# CAN.net
KiCad netlist of a schematic drawn in Altium Designer
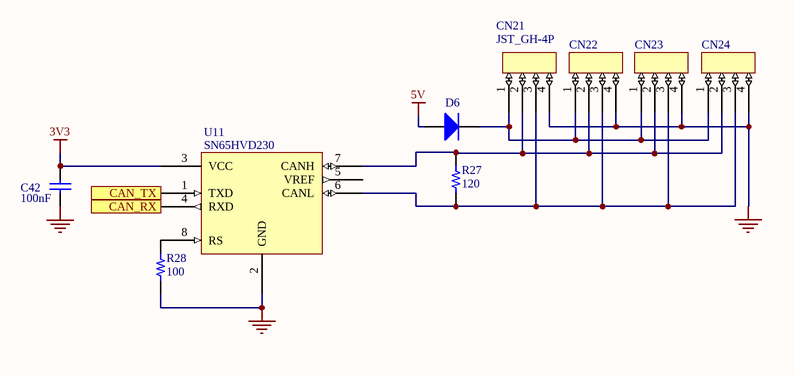
[diagram p0: CAN.SchDoc]

(export (version "E")
  (design (tool "Eeschema 10.0.6"))
  (components
    (comp (ref "C42")
      (value "100nF")
      (footprint "0402")
      (fields (field (name "Comment") "Cap") (field (name "PUBLISHER") "Altium Limited"))
      (libsource (lib "Parts") (part "Cap"))
    )
    (comp (ref "CN21")
      (value "JST_GH-4P")
      (footprint "JST_GH-4P")
      (libsource (lib "Parts") (part "JST_GH-4P"))
    )
    (comp (ref "CN22")
      (value "JST_GH-4P")
      (footprint "JST_GH-4P")
      (libsource (lib "Parts") (part "JST_GH-4P"))
    )
    (comp (ref "CN23")
      (value "JST_GH-4P")
      (footprint "JST_GH-4P")
      (libsource (lib "Parts") (part "JST_GH-4P"))
    )
    (comp (ref "CN24")
      (value "JST_GH-4P")
      (footprint "JST_GH-4P")
      (libsource (lib "Parts") (part "JST_GH-4P"))
    )
    (comp (ref "D6") (value "SS12F") (footprint "SMAF_DIODE") (libsource (lib "Parts") (part "SS12F")))
    (comp (ref "R27")
      (value "120")
      (footprint "2010_SMD_Resistor")
      (libsource (lib "Parts") (part "Resistor"))
    )
    (comp (ref "R28")
      (value "100")
      (footprint "0805 - duplicate")
      (libsource (lib "Parts") (part "Resistor"))
    )
    (comp (ref "U11")
      (value "SN65HVD230")
      (footprint "SOIC8-TI_CAN")
      (description "CAN Transceiver")
      (libsource (lib "Parts") (part "SN65HVD230"))
    )
  )
  (nets
    (net (code "1") (name "/CAN_RX") (class "Default")
      (node (ref "U11") (pin "4") (pinfunction "RXD_4") (pintype "output"))
    )
    (net (code "2") (name "/CAN_TX") (class "Default")
      (node (ref "U11") (pin "1") (pinfunction "TXD_1") (pintype "input"))
    )
    (net (code "3") (name "3V3") (class "Default")
      (node (ref "C42") (pin "2") (pinfunction "2_2") (pintype "passive"))
      (node (ref "U11") (pin "3") (pinfunction "VCC_3") (pintype "power_in"))
    )
    (net (code "4") (name "5V") (class "Default")
      (node (ref "D6") (pin "1") (pinfunction "A_1") (pintype "passive"))
    )
    (net (code "5") (name "GND") (class "Default")
      (node (ref "C42") (pin "1") (pinfunction "1_1") (pintype "passive"))
      (node (ref "CN21") (pin "4") (pintype "bidirectional"))
      (node (ref "CN22") (pin "4") (pintype "bidirectional"))
      (node (ref "CN23") (pin "4") (pintype "bidirectional"))
      (node (ref "CN24") (pin "4") (pintype "bidirectional"))
      (node (ref "R28") (pin "1") (pinfunction "1_1") (pintype "passive"))
      (node (ref "U11") (pin "2") (pinfunction "GND_2") (pintype "power_in"))
    )
    (net (code "6") (name "Net-(D6-K)") (class "Default")
      (node (ref "CN21") (pin "1") (pintype "bidirectional"))
      (node (ref "CN22") (pin "1") (pintype "bidirectional"))
      (node (ref "CN23") (pin "1") (pintype "bidirectional"))
      (node (ref "CN24") (pin "1") (pintype "bidirectional"))
      (node (ref "D6") (pin "2") (pinfunction "K_2") (pintype "passive"))
    )
    (net (code "7") (name "Net-(U11-CANH)") (class "Default")
      (node (ref "CN21") (pin "2") (pintype "bidirectional"))
      (node (ref "CN22") (pin "2") (pintype "bidirectional"))
      (node (ref "CN23") (pin "2") (pintype "bidirectional"))
      (node (ref "CN24") (pin "2") (pintype "bidirectional"))
      (node (ref "R27") (pin "2") (pinfunction "2_2") (pintype "passive"))
      (node (ref "U11") (pin "7") (pinfunction "CANH_7") (pintype "bidirectional"))
    )
    (net (code "8") (name "Net-(U11-CANL)") (class "Default")
      (node (ref "CN21") (pin "3") (pintype "bidirectional"))
      (node (ref "CN22") (pin "3") (pintype "bidirectional"))
      (node (ref "CN23") (pin "3") (pintype "bidirectional"))
      (node (ref "CN24") (pin "3") (pintype "bidirectional"))
      (node (ref "R27") (pin "1") (pinfunction "1_1") (pintype "passive"))
      (node (ref "U11") (pin "6") (pinfunction "CANL_6") (pintype "bidirectional"))
    )
    (net (code "9") (name "Net-(U11-RS)") (class "Default")
      (node (ref "R28") (pin "2") (pinfunction "2_2") (pintype "passive"))
      (node (ref "U11") (pin "8") (pinfunction "RS_8") (pintype "input"))
    )
    (net (code "10") (name "unconnected-(U11-VREF-Pad5)") (class "Default")
      (node (ref "U11") (pin "5") (pinfunction "VREF_5") (pintype "output"))
    )
  )
)
